# Sheet1.net
KiCad netlist of a schematic drawn in Altium Designer
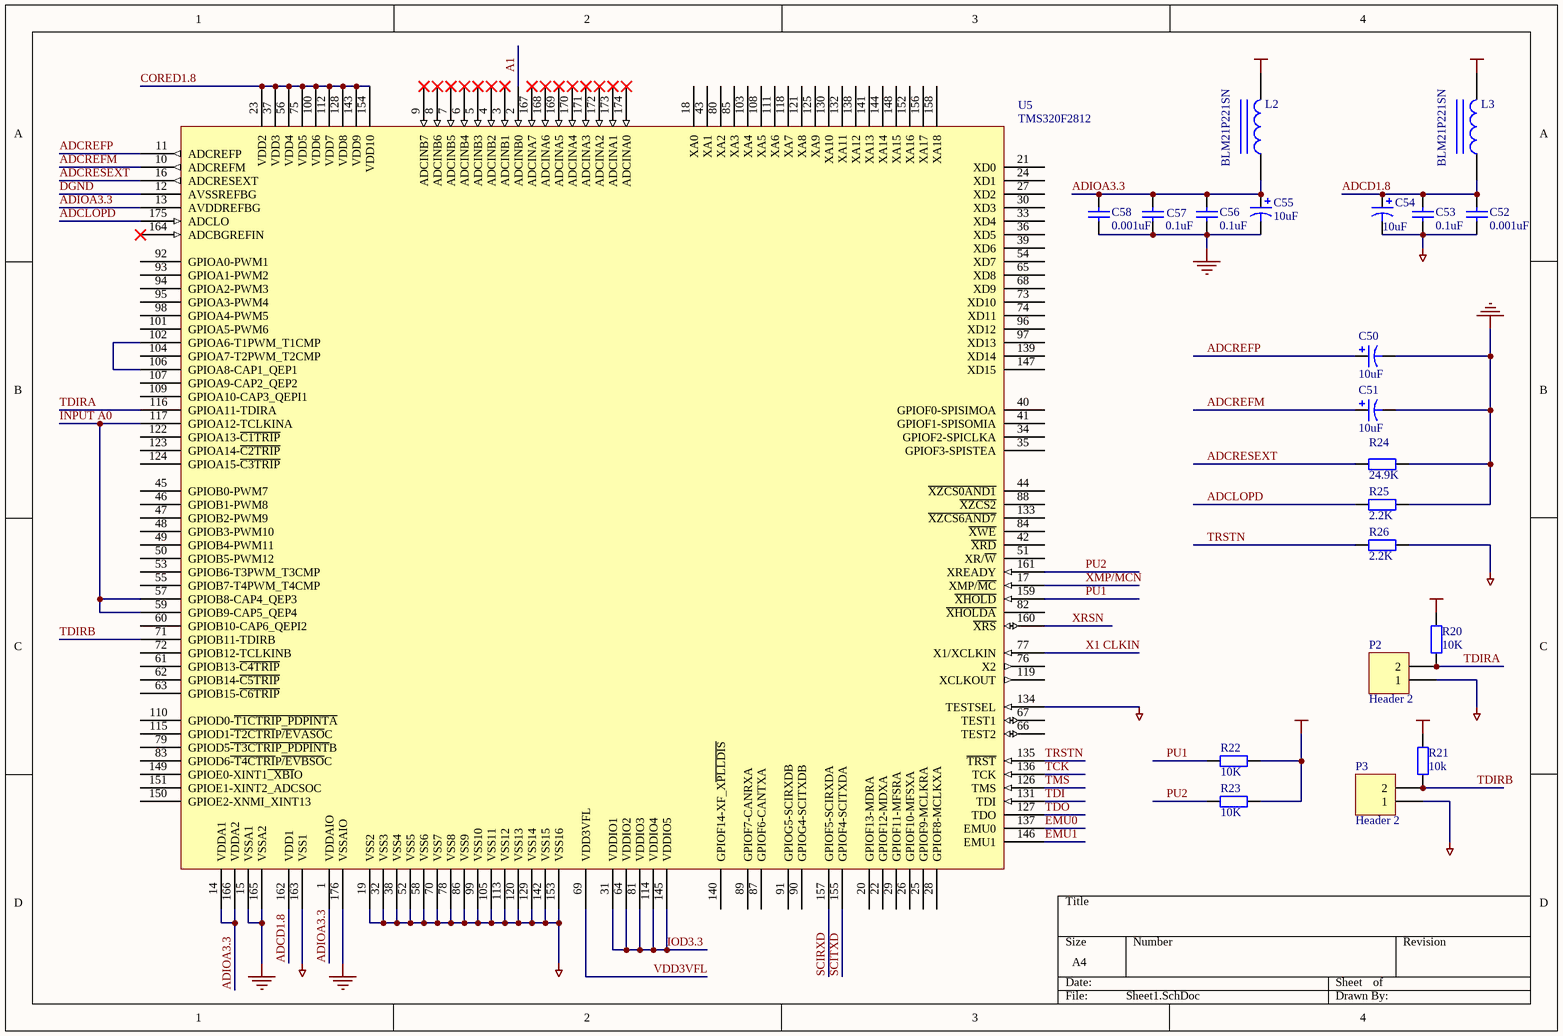
[diagram p0: Sheet1.SchDoc]

(export (version "E")
  (design (tool "Eeschema 10.0.6"))
  (components
    (comp (ref "C50")
      (value "10uF")
      (footprint "CA2222-0370")
      (description "Polarized Capacitor (Surface Mount)")
      (fields (field (name "PUBLISHER") "Altium Limited"))
      (libsource (lib "Miscellaneous Devices") (part "Cap Pol3"))
    )
    (comp (ref "C51")
      (value "10uF")
      (footprint "CA2222-0370")
      (description "Polarized Capacitor (Surface Mount)")
      (fields (field (name "PUBLISHER") "Altium Limited"))
      (libsource (lib "Miscellaneous Devices") (part "Cap Pol3"))
    )
    (comp (ref "C52")
      (value "0.001uF")
      (footprint "CC2012-0805")
      (description "Capacitor")
      (fields (field (name "PUBLISHER") "Altium Limited"))
      (libsource (lib "Miscellaneous Devices") (part "Cap"))
    )
    (comp (ref "C53")
      (value "0.1uF")
      (footprint "CC2012-0805")
      (description "Capacitor")
      (fields (field (name "PUBLISHER") "Altium Limited"))
      (libsource (lib "Miscellaneous Devices") (part "Cap"))
    )
    (comp (ref "C54")
      (value "10uF")
      (footprint "CA2222-0370")
      (description "Polarized Capacitor (Surface Mount)")
      (fields (field (name "PUBLISHER") "Altium Limited"))
      (libsource (lib "Miscellaneous Devices") (part "Cap Pol3"))
    )
    (comp (ref "C55")
      (value "10uF")
      (footprint "CA2222-0370")
      (description "Polarized Capacitor (Surface Mount)")
      (fields (field (name "PUBLISHER") "Altium Limited"))
      (libsource (lib "Miscellaneous Devices") (part "Cap Pol3"))
    )
    (comp (ref "C56")
      (value "0.1uF")
      (footprint "CC2012-0805")
      (description "Capacitor")
      (fields (field (name "PUBLISHER") "Altium Limited"))
      (libsource (lib "Miscellaneous Devices") (part "Cap"))
    )
    (comp (ref "C57")
      (value "0.1uF")
      (footprint "CC2012-0805")
      (description "Capacitor")
      (fields (field (name "PUBLISHER") "Altium Limited"))
      (libsource (lib "Miscellaneous Devices") (part "Cap"))
    )
    (comp (ref "C58")
      (value "0.001uF")
      (footprint "CC2012-0805")
      (description "Capacitor")
      (fields (field (name "PUBLISHER") "Altium Limited"))
      (libsource (lib "Miscellaneous Devices") (part "Cap"))
    )
    (comp (ref "L2")
      (value "BLM21P221SN")
      (footprint "CR2012-0805")
      (description "Magnetic-Core Inductor")
      (fields (field (name "PUBLISHER") "Altium Limited"))
      (libsource (lib "Miscellaneous Devices") (part "Inductor Iron"))
    )
    (comp (ref "L3")
      (value "BLM21P221SN")
      (footprint "CR2012-0805")
      (description "Magnetic-Core Inductor")
      (fields (field (name "PUBLISHER") "Altium Limited"))
      (libsource (lib "Miscellaneous Devices") (part "Inductor Iron"))
    )
    (comp (ref "P2")
      (value "Header 2")
      (footprint "HDR1X2")
      (description "Header, 2-Pin")
      (fields (field (name "PUBLISHER") "Altium Limited"))
      (libsource (lib "Miscellaneous Connectors") (part "Header 2"))
    )
    (comp (ref "P3")
      (value "Header 2")
      (footprint "HDR1X2")
      (description "Header, 2-Pin")
      (fields (field (name "PUBLISHER") "Altium Limited"))
      (libsource (lib "Miscellaneous Connectors") (part "Header 2"))
    )
    (comp (ref "R20")
      (value "10K")
      (footprint "CR2012-0805")
      (description "Resistor")
      (fields (field (name "PUBLISHER") "Altium Limited"))
      (libsource (lib "") (part "Res2_1"))
    )
    (comp (ref "R21")
      (value "10k")
      (footprint "CR2012-0805")
      (description "Resistor")
      (fields (field (name "PUBLISHER") "Altium Limited"))
      (libsource (lib "") (part "Res2_1"))
    )
    (comp (ref "R22")
      (value "10K")
      (footprint "CR2012-0805")
      (description "Resistor")
      (fields (field (name "PUBLISHER") "Altium Limited"))
      (libsource (lib "Miscellaneous Devices") (part "Res2"))
    )
    (comp (ref "R23")
      (value "10K")
      (footprint "CR2012-0805")
      (description "Resistor")
      (fields (field (name "PUBLISHER") "Altium Limited"))
      (libsource (lib "Miscellaneous Devices") (part "Res2"))
    )
    (comp (ref "R24")
      (value "24.9K")
      (footprint "CR2012-0805")
      (description "Resistor")
      (fields (field (name "PUBLISHER") "Altium Limited"))
      (libsource (lib "Miscellaneous Devices") (part "Res2"))
    )
    (comp (ref "R25")
      (value "2.2K")
      (footprint "CR2012-0805")
      (description "Resistor")
      (fields (field (name "PUBLISHER") "Altium Limited"))
      (libsource (lib "Miscellaneous Devices") (part "Res2"))
    )
    (comp (ref "R26")
      (value "2.2K")
      (footprint "CR2012-0805")
      (description "Resistor")
      (fields (field (name "PUBLISHER") "Altium Limited"))
      (libsource (lib "Miscellaneous Devices") (part "Res2"))
    )
    (comp (ref "U5")
      (value "TMS320F2812")
      (footprint "TMS320F2812PGFA")
      (libsource (lib "MyIntLib") (part "TMS320F2812PGF"))
    )
  )
  (nets
    (net (code "1") (name "/A1") (class "Default")
      (node (ref "U5") (pin "2") (pinfunction "ADCINB0_2") (pintype "input"))
    )
    (net (code "2") (name "/ADCD1.8") (class "Default")
      (node (ref "C52") (pin "1") (pinfunction "1_1") (pintype "passive"))
      (node (ref "C53") (pin "2") (pinfunction "2_2") (pintype "passive"))
      (node (ref "C54") (pin "1") (pinfunction "1_1") (pintype "passive"))
      (node (ref "L3") (pin "1") (pinfunction "1_1") (pintype "passive"))
      (node (ref "U5") (pin "162") (pinfunction "VDD1_162") (pintype "power_in"))
    )
    (net (code "3") (name "/ADCLOPD") (class "Default")
      (node (ref "R25") (pin "1") (pinfunction "1_1") (pintype "passive"))
      (node (ref "U5") (pin "175") (pinfunction "ADCLO_175") (pintype "input"))
    )
    (net (code "4") (name "/ADCREFM") (class "Default")
      (node (ref "C51") (pin "1") (pinfunction "1_1") (pintype "passive"))
      (node (ref "U5") (pin "10") (pinfunction "ADCREFM_10") (pintype "output"))
    )
    (net (code "5") (name "/ADCREFP") (class "Default")
      (node (ref "C50") (pin "1") (pinfunction "1_1") (pintype "passive"))
      (node (ref "U5") (pin "11") (pinfunction "ADCREFP_11") (pintype "output"))
    )
    (net (code "6") (name "/ADCRESEXT") (class "Default")
      (node (ref "R24") (pin "1") (pinfunction "1_1") (pintype "passive"))
      (node (ref "U5") (pin "16") (pinfunction "ADCRESEXT_16") (pintype "output"))
    )
    (net (code "7") (name "/ADIOA3.3") (class "Default")
      (node (ref "C55") (pin "1") (pinfunction "1_1") (pintype "passive"))
      (node (ref "C56") (pin "2") (pinfunction "2_2") (pintype "passive"))
      (node (ref "C57") (pin "2") (pinfunction "2_2") (pintype "passive"))
      (node (ref "C58") (pin "2") (pinfunction "2_2") (pintype "passive"))
      (node (ref "L2") (pin "1") (pinfunction "1_1") (pintype "passive"))
      (node (ref "U5") (pin "1") (pinfunction "VDDAIO_1") (pintype "power_in"))
      (node (ref "U5") (pin "13") (pinfunction "AVDDREFBG_13") (pintype "power_in"))
      (node (ref "U5") (pin "14") (pinfunction "VDDA1_14") (pintype "power_in"))
      (node (ref "U5") (pin "166") (pinfunction "VDDA2_166") (pintype "power_in"))
    )
    (net (code "8") (name "/CORED1.8") (class "Default")
      (node (ref "U5") (pin "100") (pinfunction "VDD6_100") (pintype "power_in"))
      (node (ref "U5") (pin "112") (pinfunction "VDD7_112") (pintype "power_in"))
      (node (ref "U5") (pin "128") (pinfunction "VDD8_128") (pintype "power_in"))
      (node (ref "U5") (pin "143") (pinfunction "VDD9_143") (pintype "power_in"))
      (node (ref "U5") (pin "154") (pinfunction "VDD10_154") (pintype "power_in"))
      (node (ref "U5") (pin "23") (pinfunction "VDD2_23") (pintype "power_in"))
      (node (ref "U5") (pin "37") (pinfunction "VDD3_37") (pintype "power_in"))
      (node (ref "U5") (pin "56") (pinfunction "VDD4_56") (pintype "power_in"))
      (node (ref "U5") (pin "75") (pinfunction "VDD5_75") (pintype "power_in"))
    )
    (net (code "9") (name "/EMU0") (class "Default")
      (node (ref "U5") (pin "137") (pinfunction "EMU0_137") (pintype "passive"))
    )
    (net (code "10") (name "/EMU1") (class "Default")
      (node (ref "U5") (pin "146") (pinfunction "EMU1_146") (pintype "passive"))
    )
    (net (code "11") (name "/INPUT A0") (class "Default")
      (node (ref "U5") (pin "117") (pinfunction "GPIOA12-TCLKINA_117") (pintype "passive"))
      (node (ref "U5") (pin "57") (pinfunction "GPIOB8-CAP4_QEP3_57") (pintype "passive"))
      (node (ref "U5") (pin "59") (pinfunction "GPIOB9-CAP5_QEP4_59") (pintype "passive"))
    )
    (net (code "12") (name "/IOD3.3") (class "Default")
      (node (ref "U5") (pin "114") (pinfunction "VDDIO4_114") (pintype "power_in"))
      (node (ref "U5") (pin "145") (pinfunction "VDDIO5_145") (pintype "power_in"))
      (node (ref "U5") (pin "31") (pinfunction "VDDIO1_31") (pintype "power_in"))
      (node (ref "U5") (pin "64") (pinfunction "VDDIO2_64") (pintype "power_in"))
      (node (ref "U5") (pin "81") (pinfunction "VDDIO3_81") (pintype "power_in"))
    )
    (net (code "13") (name "/PU1") (class "Default")
      (node (ref "R22") (pin "1") (pinfunction "1_1") (pintype "passive"))
      (node (ref "U5") (pin "159") (pinfunction "~{XHOLD}_159") (pintype "input"))
    )
    (net (code "14") (name "/PU2") (class "Default")
      (node (ref "R23") (pin "1") (pinfunction "1_1") (pintype "passive"))
      (node (ref "U5") (pin "161") (pinfunction "XREADY_161") (pintype "input"))
    )
    (net (code "15") (name "/SCIRXD") (class "Default")
      (node (ref "U5") (pin "157") (pinfunction "GPIOF5-SCIRXDA_157") (pintype "passive"))
    )
    (net (code "16") (name "/SCITXD") (class "Default")
      (node (ref "U5") (pin "155") (pinfunction "GPIOF4-SCITXDA_155") (pintype "passive"))
    )
    (net (code "17") (name "/TCK") (class "Default")
      (node (ref "U5") (pin "136") (pinfunction "TCK_136") (pintype "input"))
    )
    (net (code "18") (name "/TDI") (class "Default")
      (node (ref "U5") (pin "131") (pinfunction "TDI_131") (pintype "input"))
    )
    (net (code "19") (name "/TDIRA") (class "Default")
      (node (ref "P2") (pin "2") (pinfunction "2_2") (pintype "passive"))
      (node (ref "R20") (pin "1") (pinfunction "1_1") (pintype "passive"))
      (node (ref "U5") (pin "116") (pinfunction "GPIOA11-TDIRA_116") (pintype "passive"))
    )
    (net (code "20") (name "/TDIRB") (class "Default")
      (node (ref "P3") (pin "2") (pinfunction "2_2") (pintype "passive"))
      (node (ref "R21") (pin "1") (pinfunction "1_1") (pintype "passive"))
      (node (ref "U5") (pin "71") (pinfunction "GPIOB11-TDIRB_71") (pintype "passive"))
    )
    (net (code "21") (name "/TDO") (class "Default")
      (node (ref "U5") (pin "127") (pinfunction "TDO_127") (pintype "passive"))
    )
    (net (code "22") (name "/TMS") (class "Default")
      (node (ref "U5") (pin "126") (pinfunction "TMS_126") (pintype "input"))
    )
    (net (code "23") (name "/TRSTN") (class "Default")
      (node (ref "R26") (pin "1") (pinfunction "1_1") (pintype "passive"))
      (node (ref "U5") (pin "135") (pinfunction "~{TRST}_135") (pintype "input"))
    )
    (net (code "24") (name "/VDD3VFL") (class "Default")
      (node (ref "U5") (pin "69") (pinfunction "VDD3VFL_69") (pintype "power_in"))
    )
    (net (code "25") (name "/X1 CLKIN") (class "Default")
      (node (ref "U5") (pin "77") (pinfunction "X1/XCLKIN_77") (pintype "input"))
    )
    (net (code "26") (name "/XMP{slash}MCN") (class "Default")
      (node (ref "U5") (pin "17") (pinfunction "XMP/~{MC}_17") (pintype "input"))
    )
    (net (code "27") (name "/XRSN") (class "Default")
      (node (ref "U5") (pin "160") (pinfunction "~{XRS}_160") (pintype "bidirectional"))
    )
    (net (code "28") (name "1.8V") (class "Default")
      (node (ref "L3") (pin "2") (pinfunction "2_2") (pintype "passive"))
    )
    (net (code "29") (name "3.3V") (class "Default")
      (node (ref "L2") (pin "2") (pinfunction "2_2") (pintype "passive"))
      (node (ref "R20") (pin "2") (pinfunction "2_2") (pintype "passive"))
      (node (ref "R21") (pin "2") (pinfunction "2_2") (pintype "passive"))
      (node (ref "R22") (pin "2") (pinfunction "2_2") (pintype "passive"))
      (node (ref "R23") (pin "2") (pinfunction "2_2") (pintype "passive"))
    )
    (net (code "30") (name "AGND") (class "Default")
      (node (ref "C50") (pin "2") (pinfunction "2_2") (pintype "passive"))
      (node (ref "C51") (pin "2") (pinfunction "2_2") (pintype "passive"))
      (node (ref "C55") (pin "2") (pinfunction "2_2") (pintype "passive"))
      (node (ref "C56") (pin "1") (pinfunction "1_1") (pintype "passive"))
      (node (ref "C57") (pin "1") (pinfunction "1_1") (pintype "passive"))
      (node (ref "C58") (pin "1") (pinfunction "1_1") (pintype "passive"))
      (node (ref "R24") (pin "2") (pinfunction "2_2") (pintype "passive"))
      (node (ref "R25") (pin "2") (pinfunction "2_2") (pintype "passive"))
      (node (ref "U5") (pin "15") (pinfunction "VSSA1_15") (pintype "power_in"))
      (node (ref "U5") (pin "165") (pinfunction "VSSA2_165") (pintype "power_in"))
      (node (ref "U5") (pin "176") (pinfunction "VSSAIO_176") (pintype "power_in"))
    )
    (net (code "31") (name "DGND") (class "Default")
      (node (ref "C52") (pin "2") (pinfunction "2_2") (pintype "passive"))
      (node (ref "C53") (pin "1") (pinfunction "1_1") (pintype "passive"))
      (node (ref "C54") (pin "2") (pinfunction "2_2") (pintype "passive"))
      (node (ref "P2") (pin "1") (pinfunction "1_1") (pintype "passive"))
      (node (ref "P3") (pin "1") (pinfunction "1_1") (pintype "passive"))
      (node (ref "R26") (pin "2") (pinfunction "2_2") (pintype "passive"))
      (node (ref "U5") (pin "105") (pinfunction "VSS11_105") (pintype "power_in"))
      (node (ref "U5") (pin "113") (pinfunction "VSS12_113") (pintype "power_in"))
      (node (ref "U5") (pin "12") (pinfunction "AVSSREFBG_12") (pintype "power_in"))
      (node (ref "U5") (pin "120") (pinfunction "VSS13_120") (pintype "power_in"))
      (node (ref "U5") (pin "129") (pinfunction "VSS14_129") (pintype "power_in"))
      (node (ref "U5") (pin "134") (pinfunction "TESTSEL_134") (pintype "input"))
      (node (ref "U5") (pin "142") (pinfunction "VSS15_142") (pintype "power_in"))
      (node (ref "U5") (pin "153") (pinfunction "VSS16_153") (pintype "power_in"))
      (node (ref "U5") (pin "163") (pinfunction "VSS1_163") (pintype "power_in"))
      (node (ref "U5") (pin "19") (pinfunction "VSS2_19") (pintype "power_in"))
      (node (ref "U5") (pin "32") (pinfunction "VSS3_32") (pintype "power_in"))
      (node (ref "U5") (pin "38") (pinfunction "VSS4_38") (pintype "power_in"))
      (node (ref "U5") (pin "52") (pinfunction "VSS5_52") (pintype "power_in"))
      (node (ref "U5") (pin "58") (pinfunction "VSS6_58") (pintype "power_in"))
      (node (ref "U5") (pin "70") (pinfunction "VSS7_70") (pintype "power_in"))
      (node (ref "U5") (pin "78") (pinfunction "VSS8_78") (pintype "power_in"))
      (node (ref "U5") (pin "86") (pinfunction "VSS9_86") (pintype "power_in"))
      (node (ref "U5") (pin "99") (pinfunction "VSS10_99") (pintype "power_in"))
    )
    (net (code "32") (name "Net-(U5-GPIOA6-T1PWM_T1CMP)") (class "Default")
      (node (ref "U5") (pin "102") (pinfunction "GPIOA6-T1PWM_T1CMP_102") (pintype "passive"))
      (node (ref "U5") (pin "106") (pinfunction "GPIOA8-CAP1_QEP1_106") (pintype "passive"))
    )
    (net (code "33") (name "unconnected-(U5-ADCBGREFIN-Pad164)") (class "Default")
      (node (ref "U5") (pin "164") (pinfunction "ADCBGREFIN_164") (pintype "input+no_connect"))
    )
    (net (code "34") (name "unconnected-(U5-ADCINA0-Pad174)") (class "Default")
      (node (ref "U5") (pin "174") (pinfunction "ADCINA0_174") (pintype "input+no_connect"))
    )
    (net (code "35") (name "unconnected-(U5-ADCINA1-Pad173)") (class "Default")
      (node (ref "U5") (pin "173") (pinfunction "ADCINA1_173") (pintype "input+no_connect"))
    )
    (net (code "36") (name "unconnected-(U5-ADCINA2-Pad172)") (class "Default")
      (node (ref "U5") (pin "172") (pinfunction "ADCINA2_172") (pintype "input+no_connect"))
    )
    (net (code "37") (name "unconnected-(U5-ADCINA3-Pad171)") (class "Default")
      (node (ref "U5") (pin "171") (pinfunction "ADCINA3_171") (pintype "input+no_connect"))
    )
    (net (code "38") (name "unconnected-(U5-ADCINA4-Pad170)") (class "Default")
      (node (ref "U5") (pin "170") (pinfunction "ADCINA4_170") (pintype "input+no_connect"))
    )
    (net (code "39") (name "unconnected-(U5-ADCINA5-Pad169)") (class "Default")
      (node (ref "U5") (pin "169") (pinfunction "ADCINA5_169") (pintype "input+no_connect"))
    )
    (net (code "40") (name "unconnected-(U5-ADCINA6-Pad168)") (class "Default")
      (node (ref "U5") (pin "168") (pinfunction "ADCINA6_168") (pintype "input+no_connect"))
    )
    (net (code "41") (name "unconnected-(U5-ADCINA7-Pad167)") (class "Default")
      (node (ref "U5") (pin "167") (pinfunction "ADCINA7_167") (pintype "input+no_connect"))
    )
    (net (code "42") (name "unconnected-(U5-ADCINB1-Pad3)") (class "Default")
      (node (ref "U5") (pin "3") (pinfunction "ADCINB1_3") (pintype "input+no_connect"))
    )
    (net (code "43") (name "unconnected-(U5-ADCINB2-Pad4)") (class "Default")
      (node (ref "U5") (pin "4") (pinfunction "ADCINB2_4") (pintype "input+no_connect"))
    )
    (net (code "44") (name "unconnected-(U5-ADCINB3-Pad5)") (class "Default")
      (node (ref "U5") (pin "5") (pinfunction "ADCINB3_5") (pintype "input+no_connect"))
    )
    (net (code "45") (name "unconnected-(U5-ADCINB4-Pad6)") (class "Default")
      (node (ref "U5") (pin "6") (pinfunction "ADCINB4_6") (pintype "input+no_connect"))
    )
    (net (code "46") (name "unconnected-(U5-ADCINB5-Pad7)") (class "Default")
      (node (ref "U5") (pin "7") (pinfunction "ADCINB5_7") (pintype "input+no_connect"))
    )
    (net (code "47") (name "unconnected-(U5-ADCINB6-Pad8)") (class "Default")
      (node (ref "U5") (pin "8") (pinfunction "ADCINB6_8") (pintype "input+no_connect"))
    )
    (net (code "48") (name "unconnected-(U5-ADCINB7-Pad9)") (class "Default")
      (node (ref "U5") (pin "9") (pinfunction "ADCINB7_9") (pintype "input+no_connect"))
    )
    (net (code "49") (name "unconnected-(U5-GPIOA0-PWM1-Pad92)") (class "Default")
      (node (ref "U5") (pin "92") (pinfunction "GPIOA0-PWM1_92") (pintype "passive"))
    )
    (net (code "50") (name "unconnected-(U5-GPIOA1-PWM2-Pad93)") (class "Default")
      (node (ref "U5") (pin "93") (pinfunction "GPIOA1-PWM2_93") (pintype "passive"))
    )
    (net (code "51") (name "unconnected-(U5-GPIOA2-PWM3-Pad94)") (class "Default")
      (node (ref "U5") (pin "94") (pinfunction "GPIOA2-PWM3_94") (pintype "passive"))
    )
    (net (code "52") (name "unconnected-(U5-GPIOA3-PWM4-Pad95)") (class "Default")
      (node (ref "U5") (pin "95") (pinfunction "GPIOA3-PWM4_95") (pintype "passive"))
    )
    (net (code "53") (name "unconnected-(U5-GPIOA4-PWM5-Pad98)") (class "Default")
      (node (ref "U5") (pin "98") (pinfunction "GPIOA4-PWM5_98") (pintype "passive"))
    )
    (net (code "54") (name "unconnected-(U5-GPIOA5-PWM6-Pad101)") (class "Default")
      (node (ref "U5") (pin "101") (pinfunction "GPIOA5-PWM6_101") (pintype "passive"))
    )
    (net (code "55") (name "unconnected-(U5-GPIOA7-T2PWM_T2CMP-Pad104)") (class "Default")
      (node (ref "U5") (pin "104") (pinfunction "GPIOA7-T2PWM_T2CMP_104") (pintype "passive"))
    )
    (net (code "56") (name "unconnected-(U5-GPIOA9-CAP2_QEP2-Pad107)") (class "Default")
      (node (ref "U5") (pin "107") (pinfunction "GPIOA9-CAP2_QEP2_107") (pintype "passive"))
    )
    (net (code "57") (name "unconnected-(U5-GPIOA10-CAP3_QEPI1-Pad109)") (class "Default")
      (node (ref "U5") (pin "109") (pinfunction "GPIOA10-CAP3_QEPI1_109") (pintype "passive"))
    )
    (net (code "58") (name "unconnected-(U5-GPIOA13-~{C1TRIP}-Pad122)") (class "Default")
      (node (ref "U5") (pin "122") (pinfunction "GPIOA13-~{C1TRIP}_122") (pintype "passive"))
    )
    (net (code "59") (name "unconnected-(U5-GPIOA14-~{C2TRIP}-Pad123)") (class "Default")
      (node (ref "U5") (pin "123") (pinfunction "GPIOA14-~{C2TRIP}_123") (pintype "passive"))
    )
    (net (code "60") (name "unconnected-(U5-GPIOA15-~{C3TRIP}-Pad124)") (class "Default")
      (node (ref "U5") (pin "124") (pinfunction "GPIOA15-~{C3TRIP}_124") (pintype "passive"))
    )
    (net (code "61") (name "unconnected-(U5-GPIOB0-PWM7-Pad45)") (class "Default")
      (node (ref "U5") (pin "45") (pinfunction "GPIOB0-PWM7_45") (pintype "passive"))
    )
    (net (code "62") (name "unconnected-(U5-GPIOB1-PWM8-Pad46)") (class "Default")
      (node (ref "U5") (pin "46") (pinfunction "GPIOB1-PWM8_46") (pintype "passive"))
    )
    (net (code "63") (name "unconnected-(U5-GPIOB2-PWM9-Pad47)") (class "Default")
      (node (ref "U5") (pin "47") (pinfunction "GPIOB2-PWM9_47") (pintype "passive"))
    )
    (net (code "64") (name "unconnected-(U5-GPIOB3-PWM10-Pad48)") (class "Default")
      (node (ref "U5") (pin "48") (pinfunction "GPIOB3-PWM10_48") (pintype "passive"))
    )
    (net (code "65") (name "unconnected-(U5-GPIOB4-PWM11-Pad49)") (class "Default")
      (node (ref "U5") (pin "49") (pinfunction "GPIOB4-PWM11_49") (pintype "passive"))
    )
    (net (code "66") (name "unconnected-(U5-GPIOB5-PWM12-Pad50)") (class "Default")
      (node (ref "U5") (pin "50") (pinfunction "GPIOB5-PWM12_50") (pintype "passive"))
    )
    (net (code "67") (name "unconnected-(U5-GPIOB6-T3PWM_T3CMP-Pad53)") (class "Default")
      (node (ref "U5") (pin "53") (pinfunction "GPIOB6-T3PWM_T3CMP_53") (pintype "passive"))
    )
    (net (code "68") (name "unconnected-(U5-GPIOB7-T4PWM_T4CMP-Pad55)") (class "Default")
      (node (ref "U5") (pin "55") (pinfunction "GPIOB7-T4PWM_T4CMP_55") (pintype "passive"))
    )
    (net (code "69") (name "unconnected-(U5-GPIOB10-CAP6_QEPI2-Pad60)") (class "Default")
      (node (ref "U5") (pin "60") (pinfunction "GPIOB10-CAP6_QEPI2_60") (pintype "passive"))
    )
    (net (code "70") (name "unconnected-(U5-GPIOB12-TCLKINB-Pad72)") (class "Default")
      (node (ref "U5") (pin "72") (pinfunction "GPIOB12-TCLKINB_72") (pintype "passive"))
    )
    (net (code "71") (name "unconnected-(U5-GPIOB13-~{C4TRIP}-Pad61)") (class "Default")
      (node (ref "U5") (pin "61") (pinfunction "GPIOB13-~{C4TRIP}_61") (pintype "passive"))
    )
    (net (code "72") (name "unconnected-(U5-GPIOB14-~{C5TRIP}-Pad62)") (class "Default")
      (node (ref "U5") (pin "62") (pinfunction "GPIOB14-~{C5TRIP}_62") (pintype "passive"))
    )
    (net (code "73") (name "unconnected-(U5-GPIOB15-~{C6TRIP}-Pad63)") (class "Default")
      (node (ref "U5") (pin "63") (pinfunction "GPIOB15-~{C6TRIP}_63") (pintype "passive"))
    )
    (net (code "74") (name "unconnected-(U5-GPIOD0-~{T1CTRIP_PDPINTA}-Pad110)") (class "Default")
      (node (ref "U5") (pin "110") (pinfunction "GPIOD0-~{T1CTRIP_PDPINTA}_110") (pintype "passive"))
    )
    (net (code "75") (name "unconnected-(U5-GPIOD1~{-T2CTRI}P~{{slash}EVASO}C-Pad115)") (class "Default")
      (node (ref "U5") (pin "115") (pinfunction "GPIOD1~{-T2CTRI}P~{/EVASO}C_115") (pintype "passive"))
    )
    (net (code "76") (name "unconnected-(U5-GPIOD5~{-T3CTRIP_PDPINT}B-Pad79)") (class "Default")
      (node (ref "U5") (pin "79") (pinfunction "GPIOD5~{-T3CTRIP_PDPINT}B_79") (pintype "passive"))
    )
    (net (code "77") (name "unconnected-(U5-GPIOD6~{-T4CTRI}P~{{slash}EVBSO}C-Pad83)") (class "Default")
      (node (ref "U5") (pin "83") (pinfunction "GPIOD6~{-T4CTRI}P~{/EVBSO}C_83") (pintype "passive"))
    )
    (net (code "78") (name "unconnected-(U5-GPIOE0-XINT1~{_XBI}O-Pad149)") (class "Default")
      (node (ref "U5") (pin "149") (pinfunction "GPIOE0-XINT1~{_XBI}O_149") (pintype "passive"))
    )
    (net (code "79") (name "unconnected-(U5-GPIOE1-XINT2_ADCSOC-Pad151)") (class "Default")
      (node (ref "U5") (pin "151") (pinfunction "GPIOE1-XINT2_ADCSOC_151") (pintype "passive"))
    )
    (net (code "80") (name "unconnected-(U5-GPIOE2-XNMI_XINT13-Pad150)") (class "Default")
      (node (ref "U5") (pin "150") (pinfunction "GPIOE2-XNMI_XINT13_150") (pintype "passive"))
    )
    (net (code "81") (name "unconnected-(U5-GPIOF0-SPISIMOA-Pad40)") (class "Default")
      (node (ref "U5") (pin "40") (pinfunction "GPIOF0-SPISIMOA_40") (pintype "passive"))
    )
    (net (code "82") (name "unconnected-(U5-GPIOF1-SPISOMIA-Pad41)") (class "Default")
      (node (ref "U5") (pin "41") (pinfunction "GPIOF1-SPISOMIA_41") (pintype "passive"))
    )
    (net (code "83") (name "unconnected-(U5-GPIOF2-SPICLKA-Pad34)") (class "Default")
      (node (ref "U5") (pin "34") (pinfunction "GPIOF2-SPICLKA_34") (pintype "passive"))
    )
    (net (code "84") (name "unconnected-(U5-GPIOF3-SPISTEA-Pad35)") (class "Default")
      (node (ref "U5") (pin "35") (pinfunction "GPIOF3-SPISTEA_35") (pintype "passive"))
    )
    (net (code "85") (name "unconnected-(U5-GPIOF6-CANTXA-Pad87)") (class "Default")
      (node (ref "U5") (pin "87") (pinfunction "GPIOF6-CANTXA_87") (pintype "passive"))
    )
    (net (code "86") (name "unconnected-(U5-GPIOF7-CANRXA-Pad89)") (class "Default")
      (node (ref "U5") (pin "89") (pinfunction "GPIOF7-CANRXA_89") (pintype "passive"))
    )
    (net (code "87") (name "unconnected-(U5-GPIOF8-MCLKXA-Pad28)") (class "Default")
      (node (ref "U5") (pin "28") (pinfunction "GPIOF8-MCLKXA_28") (pintype "passive"))
    )
    (net (code "88") (name "unconnected-(U5-GPIOF9-MCLKRA-Pad25)") (class "Default")
      (node (ref "U5") (pin "25") (pinfunction "GPIOF9-MCLKRA_25") (pintype "passive"))
    )
    (net (code "89") (name "unconnected-(U5-GPIOF10-MFSXA-Pad26)") (class "Default")
      (node (ref "U5") (pin "26") (pinfunction "GPIOF10-MFSXA_26") (pintype "passive"))
    )
    (net (code "90") (name "unconnected-(U5-GPIOF11-MFSRA-Pad29)") (class "Default")
      (node (ref "U5") (pin "29") (pinfunction "GPIOF11-MFSRA_29") (pintype "passive"))
    )
    (net (code "91") (name "unconnected-(U5-GPIOF12-MDXA-Pad22)") (class "Default")
      (node (ref "U5") (pin "22") (pinfunction "GPIOF12-MDXA_22") (pintype "passive"))
    )
    (net (code "92") (name "unconnected-(U5-GPIOF13-MDRA-Pad20)") (class "Default")
      (node (ref "U5") (pin "20") (pinfunction "GPIOF13-MDRA_20") (pintype "passive"))
    )
    (net (code "93") (name "unconnected-(U5-GPIOF14-XF_X~{PLLDIS}-Pad140)") (class "Default")
      (node (ref "U5") (pin "140") (pinfunction "GPIOF14-XF_X~{PLLDIS}_140") (pintype "passive"))
    )
    (net (code "94") (name "unconnected-(U5-GPIOG4-SCITXDB-Pad90)") (class "Default")
      (node (ref "U5") (pin "90") (pinfunction "GPIOG4-SCITXDB_90") (pintype "passive"))
    )
    (net (code "95") (name "unconnected-(U5-GPIOG5-SCIRXDB-Pad91)") (class "Default")
      (node (ref "U5") (pin "91") (pinfunction "GPIOG5-SCIRXDB_91") (pintype "passive"))
    )
    (net (code "96") (name "unconnected-(U5-TEST1-Pad67)") (class "Default")
      (node (ref "U5") (pin "67") (pinfunction "TEST1_67") (pintype "bidirectional"))
    )
    (net (code "97") (name "unconnected-(U5-TEST2-Pad66)") (class "Default")
      (node (ref "U5") (pin "66") (pinfunction "TEST2_66") (pintype "bidirectional"))
    )
    (net (code "98") (name "unconnected-(U5-X2-Pad76)") (class "Default")
      (node (ref "U5") (pin "76") (pinfunction "X2_76") (pintype "output"))
    )
    (net (code "99") (name "unconnected-(U5-XA0-Pad18)") (class "Default")
      (node (ref "U5") (pin "18") (pinfunction "XA0_18") (pintype "passive"))
    )
    (net (code "100") (name "unconnected-(U5-XA1-Pad43)") (class "Default")
      (node (ref "U5") (pin "43") (pinfunction "XA1_43") (pintype "passive"))
    )
    (net (code "101") (name "unconnected-(U5-XA2-Pad80)") (class "Default")
      (node (ref "U5") (pin "80") (pinfunction "XA2_80") (pintype "passive"))
    )
    (net (code "102") (name "unconnected-(U5-XA3-Pad85)") (class "Default")
      (node (ref "U5") (pin "85") (pinfunction "XA3_85") (pintype "passive"))
    )
    (net (code "103") (name "unconnected-(U5-XA4-Pad103)") (class "Default")
      (node (ref "U5") (pin "103") (pinfunction "XA4_103") (pintype "passive"))
    )
    (net (code "104") (name "unconnected-(U5-XA5-Pad108)") (class "Default")
      (node (ref "U5") (pin "108") (pinfunction "XA5_108") (pintype "passive"))
    )
    (net (code "105") (name "unconnected-(U5-XA6-Pad111)") (class "Default")
      (node (ref "U5") (pin "111") (pinfunction "XA6_111") (pintype "passive"))
    )
    (net (code "106") (name "unconnected-(U5-XA7-Pad118)") (class "Default")
      (node (ref "U5") (pin "118") (pinfunction "XA7_118") (pintype "passive"))
    )
    (net (code "107") (name "unconnected-(U5-XA8-Pad121)") (class "Default")
      (node (ref "U5") (pin "121") (pinfunction "XA8_121") (pintype "passive"))
    )
    (net (code "108") (name "unconnected-(U5-XA9-Pad125)") (class "Default")
      (node (ref "U5") (pin "125") (pinfunction "XA9_125") (pintype "passive"))
    )
    (net (code "109") (name "unconnected-(U5-XA10-Pad130)") (class "Default")
      (node (ref "U5") (pin "130") (pinfunction "XA10_130") (pintype "passive"))
    )
    (net (code "110") (name "unconnected-(U5-XA11-Pad132)") (class "Default")
      (node (ref "U5") (pin "132") (pinfunction "XA11_132") (pintype "passive"))
    )
    (net (code "111") (name "unconnected-(U5-XA12-Pad138)") (class "Default")
      (node (ref "U5") (pin "138") (pinfunction "XA12_138") (pintype "passive"))
    )
    (net (code "112") (name "unconnected-(U5-XA13-Pad141)") (class "Default")
      (node (ref "U5") (pin "141") (pinfunction "XA13_141") (pintype "passive"))
    )
    (net (code "113") (name "unconnected-(U5-XA14-Pad144)") (class "Default")
      (node (ref "U5") (pin "144") (pinfunction "XA14_144") (pintype "passive"))
    )
    (net (code "114") (name "unconnected-(U5-XA15-Pad148)") (class "Default")
      (node (ref "U5") (pin "148") (pinfunction "XA15_148") (pintype "passive"))
    )
    (net (code "115") (name "unconnected-(U5-XA16-Pad152)") (class "Default")
      (node (ref "U5") (pin "152") (pinfunction "XA16_152") (pintype "passive"))
    )
    (net (code "116") (name "unconnected-(U5-XA17-Pad156)") (class "Default")
      (node (ref "U5") (pin "156") (pinfunction "XA17_156") (pintype "passive"))
    )
    (net (code "117") (name "unconnected-(U5-XA18-Pad158)") (class "Default")
      (node (ref "U5") (pin "158") (pinfunction "XA18_158") (pintype "passive"))
    )
    (net (code "118") (name "unconnected-(U5-XCLKOUT-Pad119)") (class "Default")
      (node (ref "U5") (pin "119") (pinfunction "XCLKOUT_119") (pintype "output"))
    )
    (net (code "119") (name "unconnected-(U5-XD0-Pad21)") (class "Default")
      (node (ref "U5") (pin "21") (pinfunction "XD0_21") (pintype "passive"))
    )
    (net (code "120") (name "unconnected-(U5-XD1-Pad24)") (class "Default")
      (node (ref "U5") (pin "24") (pinfunction "XD1_24") (pintype "passive"))
    )
    (net (code "121") (name "unconnected-(U5-XD2-Pad27)") (class "Default")
      (node (ref "U5") (pin "27") (pinfunction "XD2_27") (pintype "passive"))
    )
    (net (code "122") (name "unconnected-(U5-XD3-Pad30)") (class "Default")
      (node (ref "U5") (pin "30") (pinfunction "XD3_30") (pintype "passive"))
    )
    (net (code "123") (name "unconnected-(U5-XD4-Pad33)") (class "Default")
      (node (ref "U5") (pin "33") (pinfunction "XD4_33") (pintype "passive"))
    )
    (net (code "124") (name "unconnected-(U5-XD5-Pad36)") (class "Default")
      (node (ref "U5") (pin "36") (pinfunction "XD5_36") (pintype "passive"))
    )
    (net (code "125") (name "unconnected-(U5-XD6-Pad39)") (class "Default")
      (node (ref "U5") (pin "39") (pinfunction "XD6_39") (pintype "passive"))
    )
    (net (code "126") (name "unconnected-(U5-XD7-Pad54)") (class "Default")
      (node (ref "U5") (pin "54") (pinfunction "XD7_54") (pintype "passive"))
    )
    (net (code "127") (name "unconnected-(U5-XD8-Pad65)") (class "Default")
      (node (ref "U5") (pin "65") (pinfunction "XD8_65") (pintype "passive"))
    )
    (net (code "128") (name "unconnected-(U5-XD9-Pad68)") (class "Default")
      (node (ref "U5") (pin "68") (pinfunction "XD9_68") (pintype "passive"))
    )
    (net (code "129") (name "unconnected-(U5-XD10-Pad73)") (class "Default")
      (node (ref "U5") (pin "73") (pinfunction "XD10_73") (pintype "passive"))
    )
    (net (code "130") (name "unconnected-(U5-XD11-Pad74)") (class "Default")
      (node (ref "U5") (pin "74") (pinfunction "XD11_74") (pintype "passive"))
    )
    (net (code "131") (name "unconnected-(U5-XD12-Pad96)") (class "Default")
      (node (ref "U5") (pin "96") (pinfunction "XD12_96") (pintype "passive"))
    )
    (net (code "132") (name "unconnected-(U5-XD13-Pad97)") (class "Default")
      (node (ref "U5") (pin "97") (pinfunction "XD13_97") (pintype "passive"))
    )
    (net (code "133") (name "unconnected-(U5-XD14-Pad139)") (class "Default")
      (node (ref "U5") (pin "139") (pinfunction "XD14_139") (pintype "passive"))
    )
    (net (code "134") (name "unconnected-(U5-XD15-Pad147)") (class "Default")
      (node (ref "U5") (pin "147") (pinfunction "XD15_147") (pintype "passive"))
    )
    (net (code "135") (name "unconnected-(U5-XR{slash}~{W}-Pad51)") (class "Default")
      (node (ref "U5") (pin "51") (pinfunction "XR/~{W}_51") (pintype "passive"))
    )
    (net (code "136") (name "unconnected-(U5-~{XHOLDA}-Pad82)") (class "Default")
      (node (ref "U5") (pin "82") (pinfunction "~{XHOLDA}_82") (pintype "passive"))
    )
    (net (code "137") (name "unconnected-(U5-~{XRD}-Pad42)") (class "Default")
      (node (ref "U5") (pin "42") (pinfunction "~{XRD}_42") (pintype "passive"))
    )
    (net (code "138") (name "unconnected-(U5-~{XWE}-Pad84)") (class "Default")
      (node (ref "U5") (pin "84") (pinfunction "~{XWE}_84") (pintype "passive"))
    )
    (net (code "139") (name "unconnected-(U5-~{XZCS0AND1}-Pad44)") (class "Default")
      (node (ref "U5") (pin "44") (pinfunction "~{XZCS0AND1}_44") (pintype "passive"))
    )
    (net (code "140") (name "unconnected-(U5-~{XZCS2}-Pad88)") (class "Default")
      (node (ref "U5") (pin "88") (pinfunction "~{XZCS2}_88") (pintype "passive"))
    )
    (net (code "141") (name "unconnected-(U5-~{XZCS6AND7}-Pad133)") (class "Default")
      (node (ref "U5") (pin "133") (pinfunction "~{XZCS6AND7}_133") (pintype "passive"))
    )
  )
)
